# version_1.net
KiCad netlist of a schematic drawn in Altium Designer
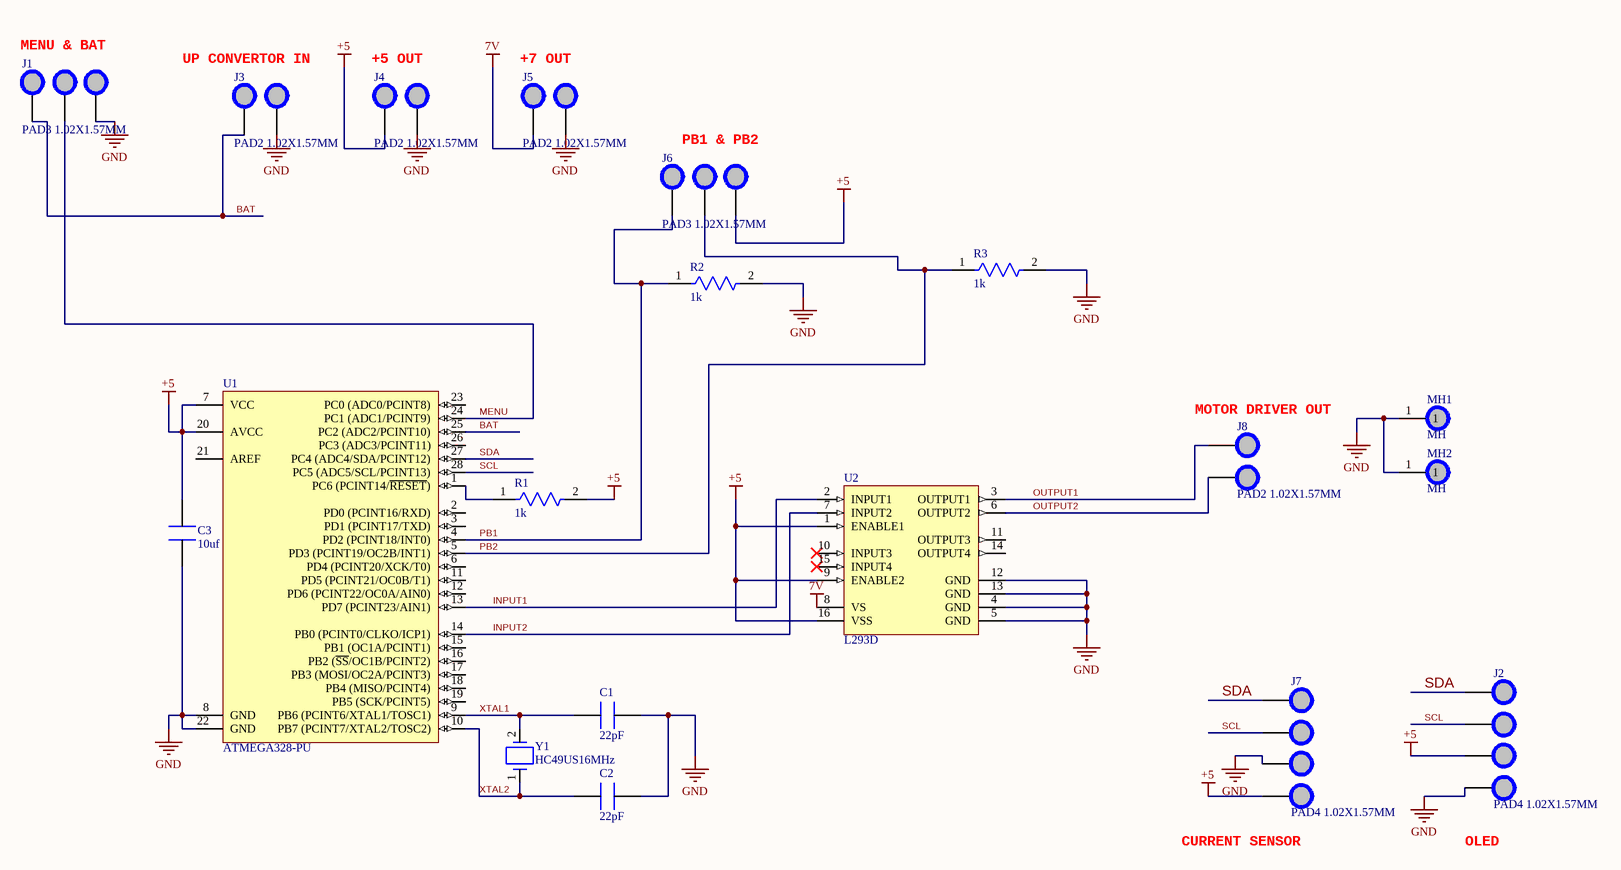
[diagram p0: version_1.SchDoc]

(export (version "E")
  (design (tool "Eeschema 10.0.6"))
  (components
    (comp (ref "C1")
      (value "22pF")
      (footprint "Capacitor_22pF")
      (description "Cap Ceramic Suppression X1/Y2 22pF 760VAC/500VAC U2J 10% (8 X 5mm) Radial 10mm 125C Bulk")
      (fields
        (field (name "MANUFACTURER") "Vishay BCcomponents")
        (field (name "MANUFACTURER PART NUMBER") "VY1220K31U2JQ63V0")
      )
      (libsource (lib "Schlib1") (part "VY1220K31U2JQ63V0"))
    )
    (comp (ref "C2")
      (value "22pF")
      (footprint "Capacitor_22pF")
      (description "Cap Ceramic Suppression X1/Y2 22pF 760VAC/500VAC U2J 10% (8 X 5mm) Radial 10mm 125C Bulk")
      (fields
        (field (name "MANUFACTURER") "Vishay BCcomponents")
        (field (name "MANUFACTURER PART NUMBER") "VY1220K31U2JQ63V0")
      )
      (libsource (lib "Schlib1") (part "VY1220K31U2JQ63V0"))
    )
    (comp (ref "C3")
      (value "10uf")
      (footprint "0805 cap")
      (fields
        (field (name "MANUFACTURER") "Samsung")
        (field (name "MANUFACTURER PART NUMBER") "CL21A106KOQNNNE")
        (field (name "TOLERANCE") "10%")
      )
      (libsource (lib "Schlib1") (part "CL21A106KOQNNNE"))
    )
    (comp (ref "J1")
      (value "PAD3 1.02X1.57MM")
      (footprint "PAD3 1.02X1.57MM")
      (libsource (lib "Schlib1") (part "PAD3 1.02X1.57MM"))
    )
    (comp (ref "J2")
      (value "PAD4 1.02X1.57MM")
      (footprint "PAD4 1.02X1.57MM")
      (libsource (lib "Schlib1") (part "PAD4 1.02X1.57MM"))
    )
    (comp (ref "J3")
      (value "PAD2 1.02X1.57MM")
      (footprint "PAD2 1.02X1.57MM")
      (libsource (lib "Schlib1") (part "PAD2 1.02X1.57MM"))
    )
    (comp (ref "J4")
      (value "PAD2 1.02X1.57MM")
      (footprint "PAD2 1.02X1.57MM")
      (libsource (lib "Schlib1") (part "PAD2 1.02X1.57MM"))
    )
    (comp (ref "J5")
      (value "PAD2 1.02X1.57MM")
      (footprint "PAD2 1.02X1.57MM")
      (libsource (lib "Schlib1") (part "PAD2 1.02X1.57MM"))
    )
    (comp (ref "J6")
      (value "PAD3 1.02X1.57MM")
      (footprint "PAD3 1.02X1.57MM")
      (libsource (lib "Schlib1") (part "PAD3 1.02X1.57MM"))
    )
    (comp (ref "J7")
      (value "PAD4 1.02X1.57MM")
      (footprint "PAD4 1.02X1.57MM")
      (libsource (lib "Schlib1") (part "PAD4 1.02X1.57MM"))
    )
    (comp (ref "J8")
      (value "PAD2 1.02X1.57MM")
      (footprint "PAD2 1.02X1.57MM")
      (libsource (lib "Schlib1") (part "PAD2 1.02X1.57MM"))
    )
    (comp (ref "MH1") (value "MH") (footprint "MH") (libsource (lib "Schlib1") (part "MH")))
    (comp (ref "MH2") (value "MH") (footprint "MH") (libsource (lib "Schlib1") (part "MH")))
    (comp (ref "R1")
      (value "1k")
      (footprint "resistor")
      (description "MRS25 Series Axial Thin Film Resistor 1kOhms +/-1% 0.6W +/-50ppm/degC")
      (fields
        (field (name "MANUFACTURER") "Vishay")
        (field (name "MANUFACTURER PART NUMBER") "MRS25000C1001FCT00")
      )
      (libsource (lib "Schlib1") (part "MRS25000C1001FCT00"))
    )
    (comp (ref "R2")
      (value "1k")
      (footprint "resistor")
      (description "MRS25 Series Axial Thin Film Resistor 1kOhms +/-1% 0.6W +/-50ppm/degC")
      (fields
        (field (name "MANUFACTURER") "Vishay")
        (field (name "MANUFACTURER PART NUMBER") "MRS25000C1001FCT00")
      )
      (libsource (lib "Schlib1") (part "MRS25000C1001FCT00"))
    )
    (comp (ref "R3")
      (value "1k")
      (footprint "resistor")
      (description "MRS25 Series Axial Thin Film Resistor 1kOhms +/-1% 0.6W +/-50ppm/degC")
      (fields
        (field (name "MANUFACTURER") "Vishay")
        (field (name "MANUFACTURER PART NUMBER") "MRS25000C1001FCT00")
      )
      (libsource (lib "Schlib1") (part "MRS25000C1001FCT00"))
    )
    (comp (ref "U1")
      (value "ATMEGA328-PU")
      (footprint "DIP28 7.62MM")
      (description "ATmega Series 32 kB Flash 2 kB SRAM 20 MHz 8-Bit Microcontroller - DIP-28")
      (fields (field (name "MANUFACTURER") "Microchip"))
      (libsource (lib "Schlib1") (part "ATMEGA328-PU"))
    )
    (comp (ref "U2")
      (value "L293D")
      (footprint "DIP16")
      (description "IC MOTOR DRIVER PAR 16-DIP")
      (fields (field (name "MANUFACTURER") "STMicroelectronics"))
      (libsource (lib "Schlib1") (part "L293D"))
    )
    (comp (ref "Y1")
      (value "HC49US16MHz")
      (footprint "HC49US16MHz")
      (fields
        (field (name "MANUFACTURER") "Citizen")
        (field (name "MANUFACTURER PART NUMBER") "HC49US16.384MABJ-UB")
      )
      (libsource (lib "Schlib1") (part "HC49US16.384MABJ-UB"))
    )
  )
  (nets
    (net (code "1") (name "+5") (class "Default")
      (node (ref "C3") (pin "2") (pinfunction "2_2") (pintype "passive"))
      (node (ref "J2") (pin "3") (pinfunction "3_3") (pintype "passive"))
      (node (ref "J4") (pin "1") (pinfunction "1_1") (pintype "passive"))
      (node (ref "J6") (pin "3") (pinfunction "3_3") (pintype "passive"))
      (node (ref "J7") (pin "4") (pinfunction "4_4") (pintype "passive"))
      (node (ref "R1") (pin "2") (pinfunction "2_2") (pintype "passive"))
      (node (ref "U1") (pin "20") (pinfunction "AVCC_20") (pintype "power_in"))
      (node (ref "U1") (pin "7") (pinfunction "VCC_7") (pintype "power_in"))
      (node (ref "U2") (pin "1") (pinfunction "ENABLE1_1") (pintype "input"))
      (node (ref "U2") (pin "16") (pinfunction "VSS_16") (pintype "passive"))
      (node (ref "U2") (pin "9") (pinfunction "ENABLE2_9") (pintype "input"))
    )
    (net (code "2") (name "/BAT") (class "Default")
      (node (ref "J1") (pin "1") (pinfunction "1_1") (pintype "passive"))
      (node (ref "J3") (pin "1") (pinfunction "1_1") (pintype "passive"))
      (node (ref "U1") (pin "25") (pinfunction "PC2_(ADC2/PCINT10)_25") (pintype "bidirectional"))
    )
    (net (code "3") (name "/INPUT1") (class "Default")
      (node (ref "U1") (pin "13") (pinfunction "PD7_(PCINT23/AIN1)_13") (pintype "bidirectional"))
      (node (ref "U2") (pin "2") (pinfunction "INPUT1_2") (pintype "input"))
    )
    (net (code "4") (name "/INPUT2") (class "Default")
      (node (ref "U1") (pin "14") (pinfunction "PB0_(PCINT0/CLKO/ICP1)_14") (pintype "bidirectional"))
      (node (ref "U2") (pin "7") (pinfunction "INPUT2_7") (pintype "input"))
    )
    (net (code "5") (name "/MENU") (class "Default")
      (node (ref "J1") (pin "2") (pinfunction "2_2") (pintype "passive"))
      (node (ref "U1") (pin "24") (pinfunction "PC1_(ADC1/PCINT9)_24") (pintype "bidirectional"))
    )
    (net (code "6") (name "/OUTPUT1") (class "Default")
      (node (ref "J8") (pin "1") (pinfunction "1_1") (pintype "passive"))
      (node (ref "U2") (pin "3") (pinfunction "OUTPUT1_3") (pintype "output"))
    )
    (net (code "7") (name "/OUTPUT2") (class "Default")
      (node (ref "J8") (pin "2") (pinfunction "2_2") (pintype "passive"))
      (node (ref "U2") (pin "6") (pinfunction "OUTPUT2_6") (pintype "output"))
    )
    (net (code "8") (name "/PB1") (class "Default")
      (node (ref "J6") (pin "1") (pinfunction "1_1") (pintype "passive"))
      (node (ref "R2") (pin "1") (pinfunction "1_1") (pintype "passive"))
      (node (ref "U1") (pin "4") (pinfunction "PD2_(PCINT18/INT0)_4") (pintype "bidirectional"))
    )
    (net (code "9") (name "/PB2") (class "Default")
      (node (ref "J6") (pin "2") (pinfunction "2_2") (pintype "passive"))
      (node (ref "R3") (pin "1") (pinfunction "1_1") (pintype "passive"))
      (node (ref "U1") (pin "5") (pinfunction "PD3_(PCINT19/OC2B/INT1)_5") (pintype "bidirectional"))
    )
    (net (code "10") (name "/SCL") (class "Default")
      (node (ref "J2") (pin "2") (pinfunction "2_2") (pintype "passive"))
      (node (ref "J7") (pin "2") (pinfunction "2_2") (pintype "passive"))
      (node (ref "U1") (pin "28") (pinfunction "PC5_(ADC5/SCL/PCINT13)_28") (pintype "bidirectional"))
    )
    (net (code "11") (name "/SDA") (class "Default")
      (node (ref "J2") (pin "1") (pinfunction "1_1") (pintype "passive"))
      (node (ref "J7") (pin "1") (pinfunction "1_1") (pintype "passive"))
      (node (ref "U1") (pin "27") (pinfunction "PC4_(ADC4/SDA/PCINT12)_27") (pintype "bidirectional"))
    )
    (net (code "12") (name "/XTAL1") (class "Default")
      (node (ref "C1") (pin "1") (pinfunction "1_1") (pintype "passive"))
      (node (ref "U1") (pin "9") (pinfunction "PB6_(PCINT6/XTAL1/TOSC1)_9") (pintype "bidirectional"))
      (node (ref "Y1") (pin "2") (pinfunction "2_2") (pintype "passive"))
    )
    (net (code "13") (name "/XTAL2") (class "Default")
      (node (ref "C2") (pin "1") (pinfunction "1_1") (pintype "passive"))
      (node (ref "U1") (pin "10") (pinfunction "PB7_(PCINT7/XTAL2/TOSC2)_10") (pintype "bidirectional"))
      (node (ref "Y1") (pin "1") (pinfunction "1_1") (pintype "passive"))
    )
    (net (code "14") (name "7V") (class "Default")
      (node (ref "J5") (pin "1") (pinfunction "1_1") (pintype "passive"))
      (node (ref "U2") (pin "8") (pinfunction "VS_8") (pintype "passive"))
    )
    (net (code "15") (name "GND") (class "Default")
      (node (ref "C1") (pin "2") (pinfunction "2_2") (pintype "passive"))
      (node (ref "C2") (pin "2") (pinfunction "2_2") (pintype "passive"))
      (node (ref "C3") (pin "1") (pinfunction "1_1") (pintype "passive"))
      (node (ref "J1") (pin "3") (pinfunction "3_3") (pintype "passive"))
      (node (ref "J2") (pin "4") (pinfunction "4_4") (pintype "passive"))
      (node (ref "J3") (pin "2") (pinfunction "2_2") (pintype "passive"))
      (node (ref "J4") (pin "2") (pinfunction "2_2") (pintype "passive"))
      (node (ref "J5") (pin "2") (pinfunction "2_2") (pintype "passive"))
      (node (ref "J7") (pin "3") (pinfunction "3_3") (pintype "passive"))
      (node (ref "MH1") (pin "1") (pinfunction "1_1") (pintype "passive"))
      (node (ref "MH2") (pin "1") (pinfunction "1_1") (pintype "passive"))
      (node (ref "R2") (pin "2") (pinfunction "2_2") (pintype "passive"))
      (node (ref "R3") (pin "2") (pinfunction "2_2") (pintype "passive"))
      (node (ref "U1") (pin "22") (pinfunction "GND_22") (pintype "power_in"))
      (node (ref "U1") (pin "8") (pinfunction "GND_8") (pintype "power_in"))
      (node (ref "U2") (pin "12") (pinfunction "GND_12") (pintype "passive"))
      (node (ref "U2") (pin "13") (pinfunction "GND_13") (pintype "passive"))
      (node (ref "U2") (pin "4") (pinfunction "GND_4") (pintype "passive"))
      (node (ref "U2") (pin "5") (pinfunction "GND_5") (pintype "passive"))
    )
    (net (code "16") (name "Net-(U1-PC6_(PCINT14{slash}~{RESET}))") (class "Default")
      (node (ref "R1") (pin "1") (pinfunction "1_1") (pintype "passive"))
      (node (ref "U1") (pin "1") (pinfunction "PC6_(PCINT14/~{RESET})_1") (pintype "bidirectional"))
    )
    (net (code "17") (name "unconnected-(U1-AREF-Pad21)") (class "Default")
      (node (ref "U1") (pin "21") (pinfunction "AREF_21") (pintype "power_in"))
    )
    (net (code "18") (name "unconnected-(U1-PB1_(OC1A{slash}PCINT1)-Pad15)") (class "Default")
      (node (ref "U1") (pin "15") (pinfunction "PB1_(OC1A/PCINT1)_15") (pintype "bidirectional"))
    )
    (net (code "19") (name "unconnected-(U1-PB2_(~{SS}{slash}OC1B{slash}PCINT2)-Pad16)") (class "Default")
      (node (ref "U1") (pin "16") (pinfunction "PB2_(~{SS}/OC1B/PCINT2)_16") (pintype "bidirectional"))
    )
    (net (code "20") (name "unconnected-(U1-PB3_(MOSI{slash}OC2A{slash}PCINT3)-Pad17)") (class "Default")
      (node (ref "U1") (pin "17") (pinfunction "PB3_(MOSI/OC2A/PCINT3)_17") (pintype "bidirectional"))
    )
    (net (code "21") (name "unconnected-(U1-PB4_(MISO{slash}PCINT4)-Pad18)") (class "Default")
      (node (ref "U1") (pin "18") (pinfunction "PB4_(MISO/PCINT4)_18") (pintype "bidirectional"))
    )
    (net (code "22") (name "unconnected-(U1-PB5_(SCK{slash}PCINT5)-Pad19)") (class "Default")
      (node (ref "U1") (pin "19") (pinfunction "PB5_(SCK/PCINT5)_19") (pintype "bidirectional"))
    )
    (net (code "23") (name "unconnected-(U1-PC0_(ADC0{slash}PCINT8)-Pad23)") (class "Default")
      (node (ref "U1") (pin "23") (pinfunction "PC0_(ADC0/PCINT8)_23") (pintype "bidirectional"))
    )
    (net (code "24") (name "unconnected-(U1-PC3_(ADC3{slash}PCINT11)-Pad26)") (class "Default")
      (node (ref "U1") (pin "26") (pinfunction "PC3_(ADC3/PCINT11)_26") (pintype "bidirectional"))
    )
    (net (code "25") (name "unconnected-(U1-PD0_(PCINT16{slash}RXD)-Pad2)") (class "Default")
      (node (ref "U1") (pin "2") (pinfunction "PD0_(PCINT16/RXD)_2") (pintype "bidirectional"))
    )
    (net (code "26") (name "unconnected-(U1-PD1_(PCINT17{slash}TXD)-Pad3)") (class "Default")
      (node (ref "U1") (pin "3") (pinfunction "PD1_(PCINT17/TXD)_3") (pintype "bidirectional"))
    )
    (net (code "27") (name "unconnected-(U1-PD4_(PCINT20{slash}XCK{slash}T0)-Pad6)") (class "Default")
      (node (ref "U1") (pin "6") (pinfunction "PD4_(PCINT20/XCK/T0)_6") (pintype "bidirectional"))
    )
    (net (code "28") (name "unconnected-(U1-PD5_(PCINT21{slash}OC0B{slash}T1)-Pad11)") (class "Default")
      (node (ref "U1") (pin "11") (pinfunction "PD5_(PCINT21/OC0B/T1)_11") (pintype "bidirectional"))
    )
    (net (code "29") (name "unconnected-(U1-PD6_(PCINT22{slash}OC0A{slash}AIN0)-Pad12)") (class "Default")
      (node (ref "U1") (pin "12") (pinfunction "PD6_(PCINT22/OC0A/AIN0)_12") (pintype "bidirectional"))
    )
    (net (code "30") (name "unconnected-(U2-INPUT3-Pad10)") (class "Default")
      (node (ref "U2") (pin "10") (pinfunction "INPUT3_10") (pintype "input+no_connect"))
    )
    (net (code "31") (name "unconnected-(U2-INPUT4-Pad15)") (class "Default")
      (node (ref "U2") (pin "15") (pinfunction "INPUT4_15") (pintype "input+no_connect"))
    )
    (net (code "32") (name "unconnected-(U2-OUTPUT3-Pad11)") (class "Default")
      (node (ref "U2") (pin "11") (pinfunction "OUTPUT3_11") (pintype "output"))
    )
    (net (code "33") (name "unconnected-(U2-OUTPUT4-Pad14)") (class "Default")
      (node (ref "U2") (pin "14") (pinfunction "OUTPUT4_14") (pintype "output"))
    )
  )
)
